# bb_pwr_knx_v-measure_v1_0_0.net
KiCad netlist of a schematic drawn in EAGLE
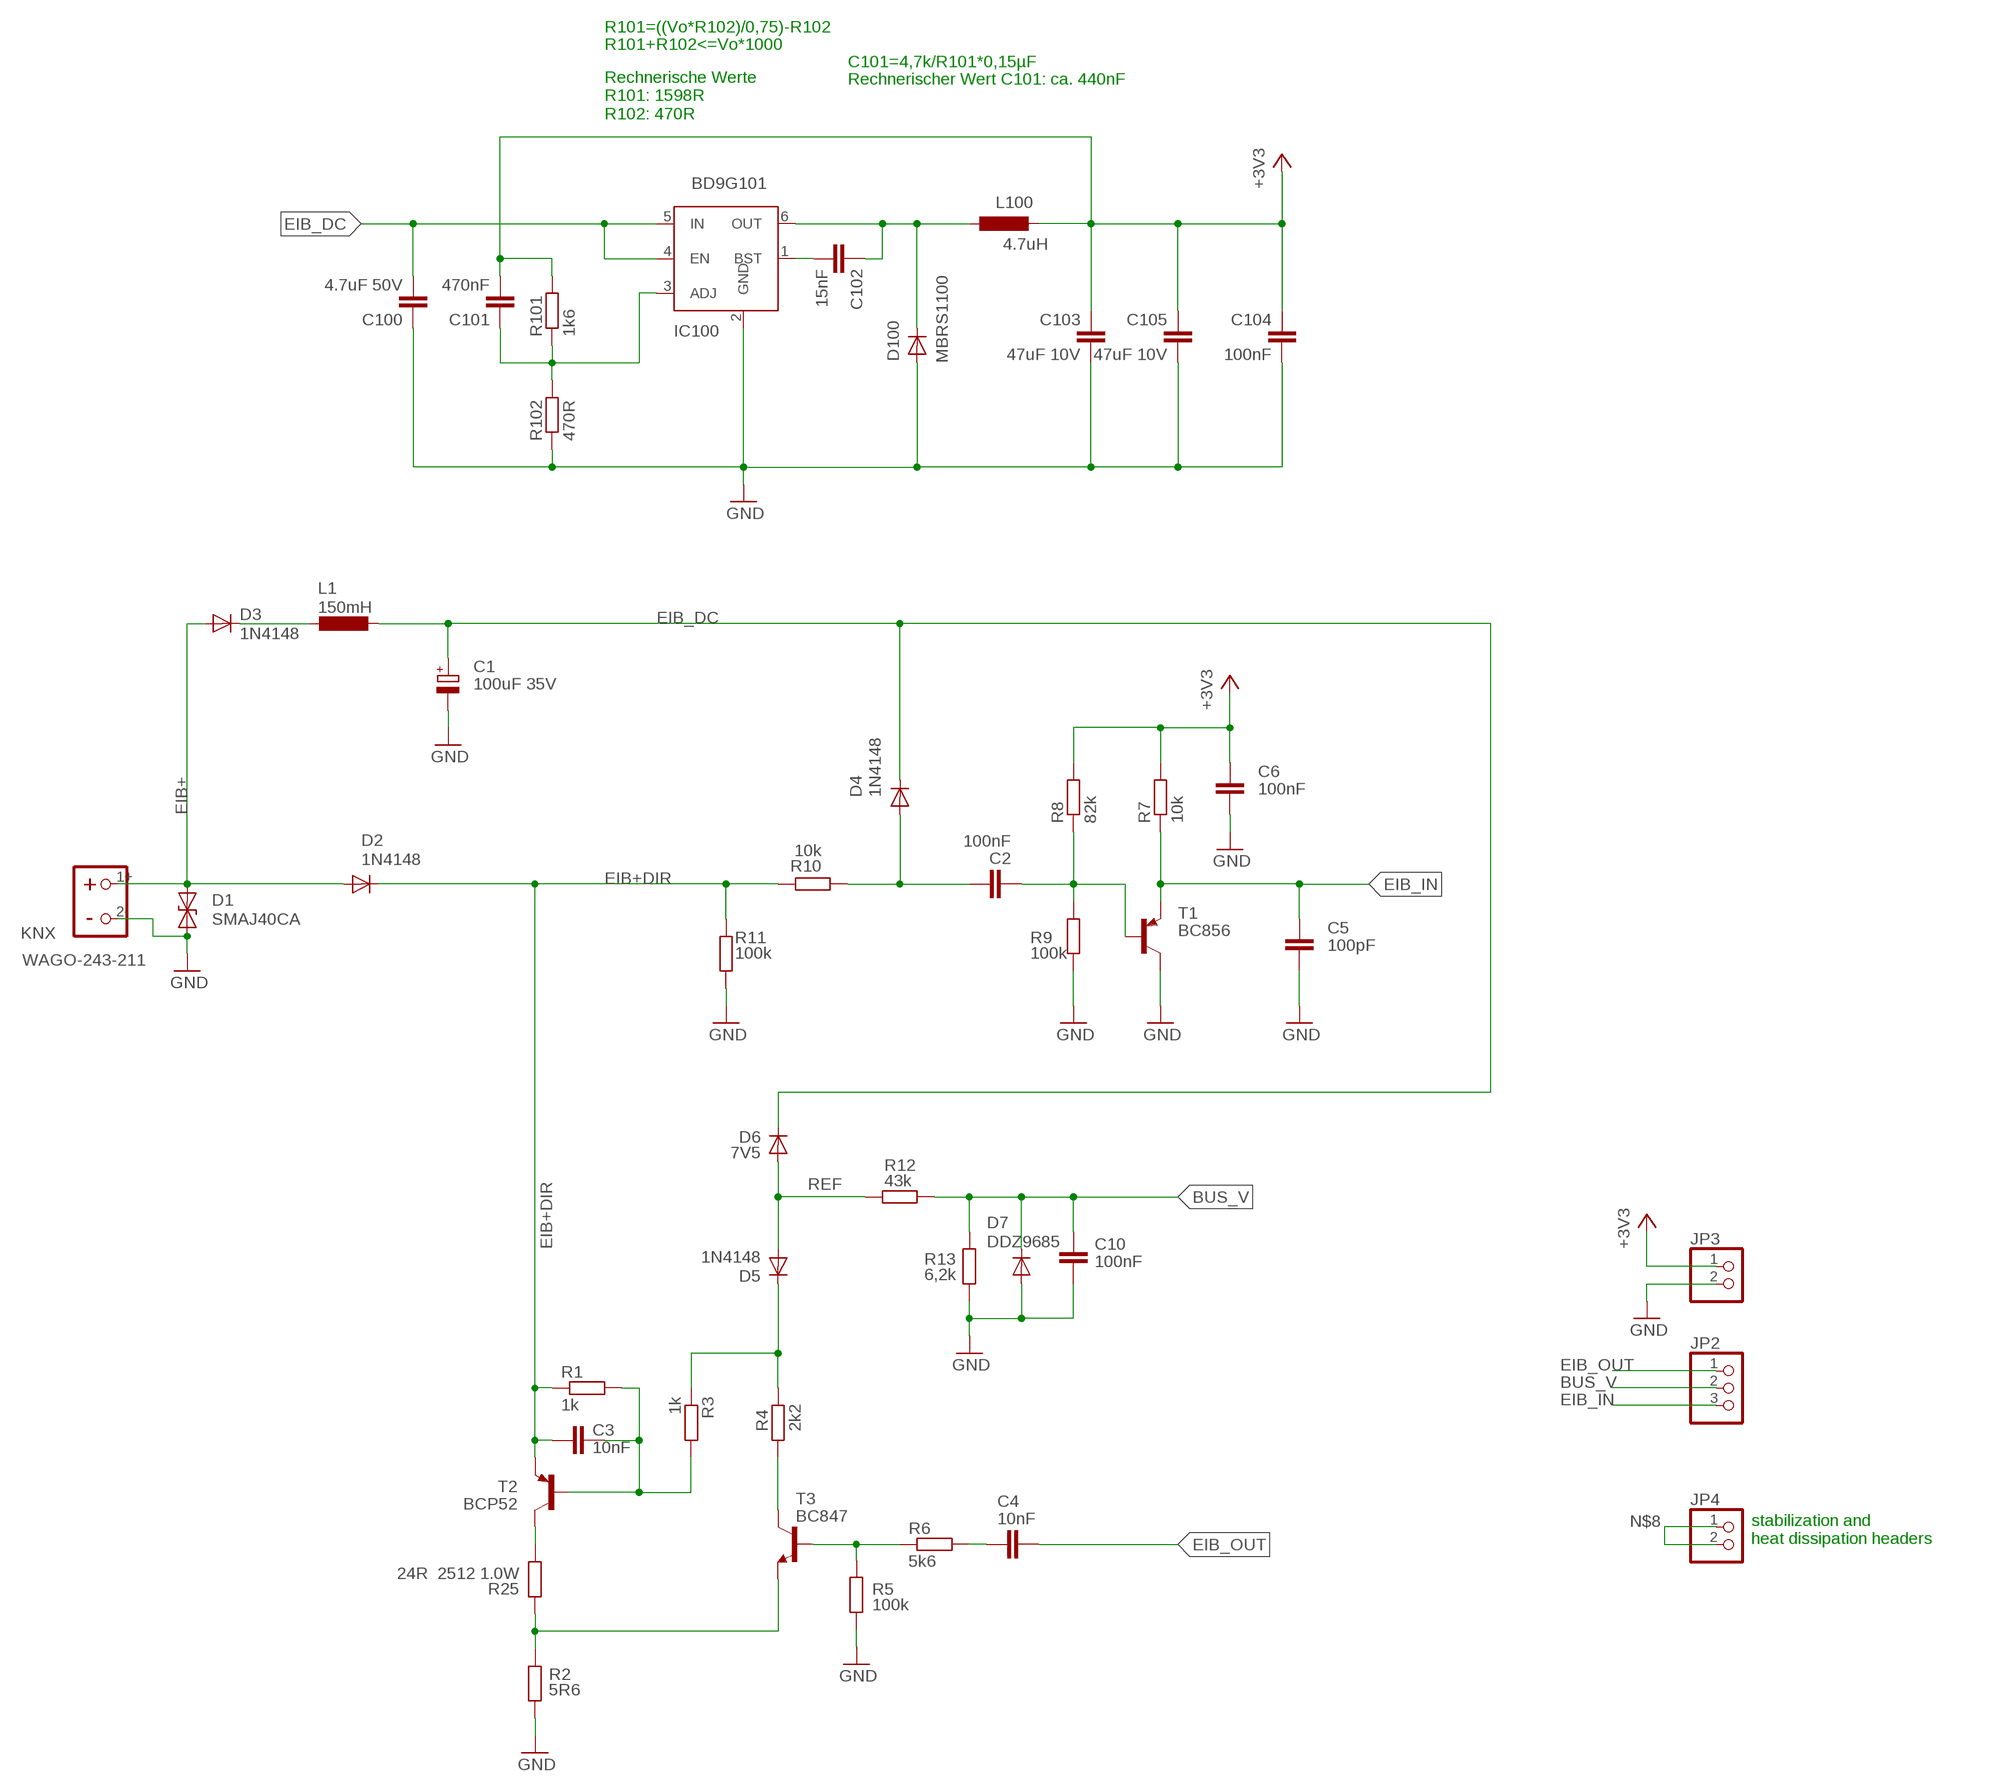
[diagram p0: schematic, sheet 1]

(export (version "E")
  (design (tool "Eeschema 10.0.6"))
  (components
    (comp (ref "C1")
      (value "100uF 35V")
      (footprint "eagle-import:SANYO-OSCON_SMD_C6")
      (libsource (lib "eagle-import") (part "CPOL-EUSANYO_SMD_C6"))
    )
    (comp (ref "C2")
      (value "100nF")
      (footprint "eagle-import:C0805")
      (libsource (lib "eagle-import") (part "C-EUC0805"))
    )
    (comp (ref "C3")
      (value "10nF")
      (footprint "eagle-import:C0805")
      (libsource (lib "eagle-import") (part "C-EUC0805"))
    )
    (comp (ref "C4")
      (value "10nF")
      (footprint "eagle-import:C0805")
      (libsource (lib "eagle-import") (part "C-EUC0805"))
    )
    (comp (ref "C5")
      (value "100pF")
      (footprint "eagle-import:C0805")
      (libsource (lib "eagle-import") (part "C-EUC0805"))
    )
    (comp (ref "C6")
      (value "100nF")
      (footprint "eagle-import:C0805")
      (libsource (lib "eagle-import") (part "C-EUC0805"))
    )
    (comp (ref "C10")
      (value "100nF")
      (footprint "eagle-import:C0805")
      (libsource (lib "eagle-import") (part "C-EUC0805"))
    )
    (comp (ref "C100")
      (value "4.7uF 50V")
      (footprint "eagle-import:C0805")
      (libsource (lib "eagle-import") (part "C-EUC0805"))
    )
    (comp (ref "C101")
      (value "470nF")
      (footprint "eagle-import:C0805")
      (libsource (lib "eagle-import") (part "C-EUC0805"))
    )
    (comp (ref "C102")
      (value "15nF")
      (footprint "eagle-import:C0805")
      (libsource (lib "eagle-import") (part "C-EUC0805"))
    )
    (comp (ref "C103")
      (value "47uF 10V")
      (footprint "eagle-import:C0805")
      (libsource (lib "eagle-import") (part "C-EUC0805"))
    )
    (comp (ref "C104")
      (value "100nF")
      (footprint "eagle-import:C0805")
      (libsource (lib "eagle-import") (part "C-EUC0805"))
    )
    (comp (ref "C105")
      (value "47uF 10V")
      (footprint "eagle-import:C0805")
      (libsource (lib "eagle-import") (part "C-EUC0805"))
    )
    (comp (ref "D1")
      (value "SMAJ40CA")
      (footprint "eagle-import:DO214AC")
      (fields (field (name "MF") "Littelfuse"))
      (libsource (lib "eagle-import") (part "SMAJCA40"))
    )
    (comp (ref "D2")
      (value "1N4148")
      (footprint "eagle-import:SOD-123")
      (libsource (lib "eagle-import") (part "DIODESOD-123"))
    )
    (comp (ref "D3")
      (value "1N4148")
      (footprint "eagle-import:SOD-123")
      (libsource (lib "eagle-import") (part "DIODESOD-123"))
    )
    (comp (ref "D4")
      (value "1N4148")
      (footprint "eagle-import:SOD-123")
      (libsource (lib "eagle-import") (part "DIODESOD-123"))
    )
    (comp (ref "D5")
      (value "1N4148")
      (footprint "eagle-import:SOD-123")
      (libsource (lib "eagle-import") (part "DIODESOD-123"))
    )
    (comp (ref "D6")
      (value "7V5")
      (footprint "eagle-import:SOD-123")
      (libsource (lib "eagle-import") (part "DIODESOD-123"))
    )
    (comp (ref "D7")
      (value "DDZ9685")
      (footprint "eagle-import:SOD-123")
      (libsource (lib "eagle-import") (part "DIODESOD-123"))
    )
    (comp (ref "D100")
      (value "MBRS1100")
      (footprint "eagle-import:SOD-123")
      (libsource (lib "eagle-import") (part "DIODESOD-123"))
    )
    (comp (ref "IC100")
      (value "BD9G101")
      (footprint "eagle-import:SOT23-6")
      (libsource (lib "eagle-import") (part "BD9G101GBD9G101G-SOT23-6"))
    )
    (comp (ref "JP2")
      (value "PINHD-1X3")
      (footprint "eagle-import:1X03")
      (libsource (lib "eagle-import") (part "PINHD-1X3"))
    )
    (comp (ref "JP3")
      (value "PINHD-1X2")
      (footprint "eagle-import:1X02")
      (libsource (lib "eagle-import") (part "PINHD-1X2"))
    )
    (comp (ref "JP4")
      (value "PINHD-1X2")
      (footprint "eagle-import:1X02")
      (libsource (lib "eagle-import") (part "PINHD-1X2"))
    )
    (comp (ref "KNX")
      (value "WAGO-243-211")
      (footprint "eagle-import:WAGO-243-211")
      (libsource (lib "eagle-import") (part "WAGO-243-211"))
    )
    (comp (ref "L1")
      (value "150mH")
      (footprint "eagle-import:11P-L1")
      (fields (field (name "SPICEPREFIX") "L"))
      (libsource (lib "eagle-import") (part "150MH-L11PL1"))
    )
    (comp (ref "L100")
      (value "4.7uH")
      (footprint "eagle-import:L4532P")
      (libsource (lib "eagle-import") (part "L-EUL4532P"))
    )
    (comp (ref "R1")
      (value "1k")
      (footprint "eagle-import:R0805")
      (libsource (lib "eagle-import") (part "R-EU_R0805"))
    )
    (comp (ref "R2")
      (value "5R6")
      (footprint "eagle-import:R0805")
      (libsource (lib "eagle-import") (part "R-EU_R0805"))
    )
    (comp (ref "R3")
      (value "1k")
      (footprint "eagle-import:R0805")
      (libsource (lib "eagle-import") (part "R-EU_R0805"))
    )
    (comp (ref "R4")
      (value "2k2")
      (footprint "eagle-import:R0805")
      (libsource (lib "eagle-import") (part "R-EU_R0805"))
    )
    (comp (ref "R5")
      (value "100k")
      (footprint "eagle-import:R0805")
      (libsource (lib "eagle-import") (part "R-EU_R0805"))
    )
    (comp (ref "R6")
      (value "5k6")
      (footprint "eagle-import:R0805")
      (libsource (lib "eagle-import") (part "R-EU_R0805"))
    )
    (comp (ref "R7")
      (value "10k")
      (footprint "eagle-import:R0805")
      (libsource (lib "eagle-import") (part "R-EU_R0805"))
    )
    (comp (ref "R8")
      (value "82k")
      (footprint "eagle-import:R0805")
      (libsource (lib "eagle-import") (part "R-EU_R0805"))
    )
    (comp (ref "R9")
      (value "100k")
      (footprint "eagle-import:R0805")
      (libsource (lib "eagle-import") (part "R-EU_R0805"))
    )
    (comp (ref "R10")
      (value "10k")
      (footprint "eagle-import:R0805")
      (libsource (lib "eagle-import") (part "R-EU_R0805"))
    )
    (comp (ref "R11")
      (value "100k")
      (footprint "eagle-import:R0805")
      (libsource (lib "eagle-import") (part "R-EU_R0805"))
    )
    (comp (ref "R12")
      (value "43k")
      (footprint "eagle-import:R0805")
      (libsource (lib "eagle-import") (part "R-EU_R0805"))
    )
    (comp (ref "R13")
      (value "6,2k")
      (footprint "eagle-import:R0805")
      (libsource (lib "eagle-import") (part "R-EU_R0805"))
    )
    (comp (ref "R25")
      (value "24R 2512 1.0W")
      (footprint "eagle-import:R2512")
      (libsource (lib "eagle-import") (part "R-EU_R2512"))
    )
    (comp (ref "R101")
      (value "1k6")
      (footprint "eagle-import:R0805")
      (libsource (lib "eagle-import") (part "R-EU_R0805"))
    )
    (comp (ref "R102")
      (value "470R")
      (footprint "eagle-import:R0805")
      (libsource (lib "eagle-import") (part "R-EU_R0805"))
    )
    (comp (ref "T1")
      (value "BC856")
      (footprint "eagle-import:SOT23-BEC")
      (libsource (lib "eagle-import") (part "BC856SMDB"))
    )
    (comp (ref "T2")
      (value "BCP52")
      (footprint "eagle-import:SOT223")
      (libsource (lib "eagle-import") (part "FZT753SMD"))
    )
    (comp (ref "T3")
      (value "BC847")
      (footprint "eagle-import:SOT23")
      (libsource (lib "eagle-import") (part "BC847"))
    )
  )
  (nets
    (net (code "1") (name "+3V3") (class "Default")
      (node (ref "C101") (pin "2") (pinfunction "2_2") (pintype "passive"))
      (node (ref "C103") (pin "1") (pinfunction "1_1") (pintype "passive"))
      (node (ref "C104") (pin "1") (pinfunction "1_1") (pintype "passive"))
      (node (ref "C105") (pin "1") (pinfunction "1_1") (pintype "passive"))
      (node (ref "C6") (pin "2") (pinfunction "2_2") (pintype "passive"))
      (node (ref "JP3") (pin "1") (pinfunction "1_1") (pintype "passive"))
      (node (ref "L100") (pin "2") (pinfunction "2_2") (pintype "passive"))
      (node (ref "R101") (pin "2") (pinfunction "2_2") (pintype "passive"))
      (node (ref "R7") (pin "2") (pinfunction "2_2") (pintype "passive"))
      (node (ref "R8") (pin "2") (pinfunction "2_2") (pintype "passive"))
    )
    (net (code "2") (name "/EIB+") (class "Default")
      (node (ref "D1") (pin "C") (pinfunction "2_C") (pintype "passive"))
      (node (ref "D2") (pin "A") (pinfunction "A_A") (pintype "passive"))
      (node (ref "D3") (pin "A") (pinfunction "A_A") (pintype "passive"))
      (node (ref "KNX") (pin "1+") (pinfunction "1+_1+") (pintype "passive"))
    )
    (net (code "3") (name "/EIB+DIR") (class "Default")
      (node (ref "C3") (pin "1") (pinfunction "1_1") (pintype "passive"))
      (node (ref "D2") (pin "C") (pinfunction "C_C") (pintype "passive"))
      (node (ref "R1") (pin "1") (pinfunction "1_1") (pintype "passive"))
      (node (ref "R10") (pin "2") (pinfunction "2_2") (pintype "passive"))
      (node (ref "R11") (pin "2") (pinfunction "2_2") (pintype "passive"))
      (node (ref "T2") (pin "3") (pinfunction "E_3") (pintype "passive"))
    )
    (net (code "4") (name "/N$8") (class "Default")
      (node (ref "JP4") (pin "1") (pinfunction "1_1") (pintype "passive"))
      (node (ref "JP4") (pin "2") (pinfunction "2_2") (pintype "passive"))
      (node (ref "R25") (pin "2") (pinfunction "2_2") (pintype "passive"))
      (node (ref "T2") (pin "2") (pinfunction "C_2") (pintype "passive"))
      (node (ref "T2") (pin "4") (pinfunction "C_4") (pintype "passive"))
    )
    (net (code "5") (name "/REF") (class "Default")
      (node (ref "D5") (pin "A") (pinfunction "A_A") (pintype "passive"))
      (node (ref "D6") (pin "A") (pinfunction "A_A") (pintype "passive"))
      (node (ref "R12") (pin "1") (pinfunction "1_1") (pintype "passive"))
    )
    (net (code "6") (name "BUS_V") (class "Default")
      (node (ref "C10") (pin "2") (pinfunction "2_2") (pintype "passive"))
      (node (ref "D7") (pin "C") (pinfunction "C_C") (pintype "passive"))
      (node (ref "JP2") (pin "2") (pinfunction "2_2") (pintype "passive"))
      (node (ref "R12") (pin "2") (pinfunction "2_2") (pintype "passive"))
      (node (ref "R13") (pin "1") (pinfunction "1_1") (pintype "passive"))
    )
    (net (code "7") (name "EIB_DC") (class "Default")
      (node (ref "C1") (pin "+") (pinfunction "+_+") (pintype "passive"))
      (node (ref "C100") (pin "2") (pinfunction "2_2") (pintype "passive"))
      (node (ref "D4") (pin "C") (pinfunction "C_C") (pintype "passive"))
      (node (ref "D6") (pin "C") (pinfunction "C_C") (pintype "passive"))
      (node (ref "IC100") (pin "4") (pinfunction "EN_4") (pintype "input"))
      (node (ref "IC100") (pin "5") (pinfunction "IN_5") (pintype "input"))
      (node (ref "L1") (pin "2") (pinfunction "2_2") (pintype "passive"))
    )
    (net (code "8") (name "EIB_IN") (class "Default")
      (node (ref "C5") (pin "2") (pinfunction "2_2") (pintype "passive"))
      (node (ref "JP2") (pin "3") (pinfunction "3_3") (pintype "passive"))
      (node (ref "R7") (pin "1") (pinfunction "1_1") (pintype "passive"))
      (node (ref "T1") (pin "E") (pinfunction "E_E") (pintype "passive"))
    )
    (net (code "9") (name "EIB_OUT") (class "Default")
      (node (ref "C4") (pin "2") (pinfunction "2_2") (pintype "passive"))
      (node (ref "JP2") (pin "1") (pinfunction "1_1") (pintype "passive"))
    )
    (net (code "10") (name "GND") (class "Default")
      (node (ref "C1") (pin "-") (pinfunction "-_-") (pintype "passive"))
      (node (ref "C10") (pin "1") (pinfunction "1_1") (pintype "passive"))
      (node (ref "C100") (pin "1") (pinfunction "1_1") (pintype "passive"))
      (node (ref "C103") (pin "2") (pinfunction "2_2") (pintype "passive"))
      (node (ref "C104") (pin "2") (pinfunction "2_2") (pintype "passive"))
      (node (ref "C105") (pin "2") (pinfunction "2_2") (pintype "passive"))
      (node (ref "C5") (pin "1") (pinfunction "1_1") (pintype "passive"))
      (node (ref "C6") (pin "1") (pinfunction "1_1") (pintype "passive"))
      (node (ref "D1") (pin "A") (pinfunction "1_A") (pintype "passive"))
      (node (ref "D100") (pin "A") (pinfunction "A_A") (pintype "passive"))
      (node (ref "D7") (pin "A") (pinfunction "A_A") (pintype "passive"))
      (node (ref "IC100") (pin "2") (pinfunction "GND_2") (pintype "power_in"))
      (node (ref "JP3") (pin "2") (pinfunction "2_2") (pintype "passive"))
      (node (ref "KNX") (pin "2-") (pinfunction "2-_2-") (pintype "passive"))
      (node (ref "R102") (pin "1") (pinfunction "1_1") (pintype "passive"))
      (node (ref "R11") (pin "1") (pinfunction "1_1") (pintype "passive"))
      (node (ref "R13") (pin "2") (pinfunction "2_2") (pintype "passive"))
      (node (ref "R2") (pin "1") (pinfunction "1_1") (pintype "passive"))
      (node (ref "R5") (pin "2") (pinfunction "2_2") (pintype "passive"))
      (node (ref "R9") (pin "1") (pinfunction "1_1") (pintype "passive"))
      (node (ref "T1") (pin "C") (pinfunction "C_C") (pintype "passive"))
    )
    (net (code "11") (name "Net-(C2-Pad1)") (class "Default")
      (node (ref "C2") (pin "1") (pinfunction "1_1") (pintype "passive"))
      (node (ref "R8") (pin "1") (pinfunction "1_1") (pintype "passive"))
      (node (ref "R9") (pin "2") (pinfunction "2_2") (pintype "passive"))
      (node (ref "T1") (pin "B") (pinfunction "B_B") (pintype "passive"))
    )
    (net (code "12") (name "Net-(C2-Pad2)") (class "Default")
      (node (ref "C2") (pin "2") (pinfunction "2_2") (pintype "passive"))
      (node (ref "D4") (pin "A") (pinfunction "A_A") (pintype "passive"))
      (node (ref "R10") (pin "1") (pinfunction "1_1") (pintype "passive"))
    )
    (net (code "13") (name "Net-(C4-Pad1)") (class "Default")
      (node (ref "C4") (pin "1") (pinfunction "1_1") (pintype "passive"))
      (node (ref "R6") (pin "2") (pinfunction "2_2") (pintype "passive"))
    )
    (net (code "14") (name "Net-(D3-PadC)") (class "Default")
      (node (ref "D3") (pin "C") (pinfunction "C_C") (pintype "passive"))
      (node (ref "L1") (pin "1") (pinfunction "1_1") (pintype "passive"))
    )
    (net (code "15") (name "Net-(D5-PadC)") (class "Default")
      (node (ref "D5") (pin "C") (pinfunction "C_C") (pintype "passive"))
      (node (ref "R3") (pin "1") (pinfunction "1_1") (pintype "passive"))
      (node (ref "R4") (pin "2") (pinfunction "2_2") (pintype "passive"))
    )
    (net (code "16") (name "Net-(IC100-ADJ)") (class "Default")
      (node (ref "C101") (pin "1") (pinfunction "1_1") (pintype "passive"))
      (node (ref "IC100") (pin "3") (pinfunction "ADJ_3") (pintype "passive"))
      (node (ref "R101") (pin "1") (pinfunction "1_1") (pintype "passive"))
      (node (ref "R102") (pin "2") (pinfunction "2_2") (pintype "passive"))
    )
    (net (code "17") (name "Net-(IC100-BST)") (class "Default")
      (node (ref "C102") (pin "2") (pinfunction "2_2") (pintype "passive"))
      (node (ref "IC100") (pin "1") (pinfunction "BST_1") (pintype "output"))
    )
    (net (code "18") (name "Net-(IC100-OUT)") (class "Default")
      (node (ref "C102") (pin "1") (pinfunction "1_1") (pintype "passive"))
      (node (ref "D100") (pin "C") (pinfunction "C_C") (pintype "passive"))
      (node (ref "IC100") (pin "6") (pinfunction "OUT_6") (pintype "output"))
      (node (ref "L100") (pin "1") (pinfunction "1_1") (pintype "passive"))
    )
    (net (code "19") (name "Net-(T2-B)") (class "Default")
      (node (ref "C3") (pin "2") (pinfunction "2_2") (pintype "passive"))
      (node (ref "R1") (pin "2") (pinfunction "2_2") (pintype "passive"))
      (node (ref "R3") (pin "2") (pinfunction "2_2") (pintype "passive"))
      (node (ref "T2") (pin "1") (pinfunction "B_1") (pintype "passive"))
    )
    (net (code "20") (name "Net-(T3-B)") (class "Default")
      (node (ref "R5") (pin "1") (pinfunction "1_1") (pintype "passive"))
      (node (ref "R6") (pin "1") (pinfunction "1_1") (pintype "passive"))
      (node (ref "T3") (pin "1") (pinfunction "B_1") (pintype "passive"))
    )
    (net (code "21") (name "Net-(T3-C)") (class "Default")
      (node (ref "R4") (pin "1") (pinfunction "1_1") (pintype "passive"))
      (node (ref "T3") (pin "3") (pinfunction "C_3") (pintype "passive"))
    )
    (net (code "22") (name "Net-(T3-E)") (class "Default")
      (node (ref "R2") (pin "2") (pinfunction "2_2") (pintype "passive"))
      (node (ref "R25") (pin "1") (pinfunction "1_1") (pintype "passive"))
      (node (ref "T3") (pin "2") (pinfunction "E_2") (pintype "passive"))
    )
  )
)
